# BIT_3.net
KiCad netlist of a schematic drawn in EasyEDA
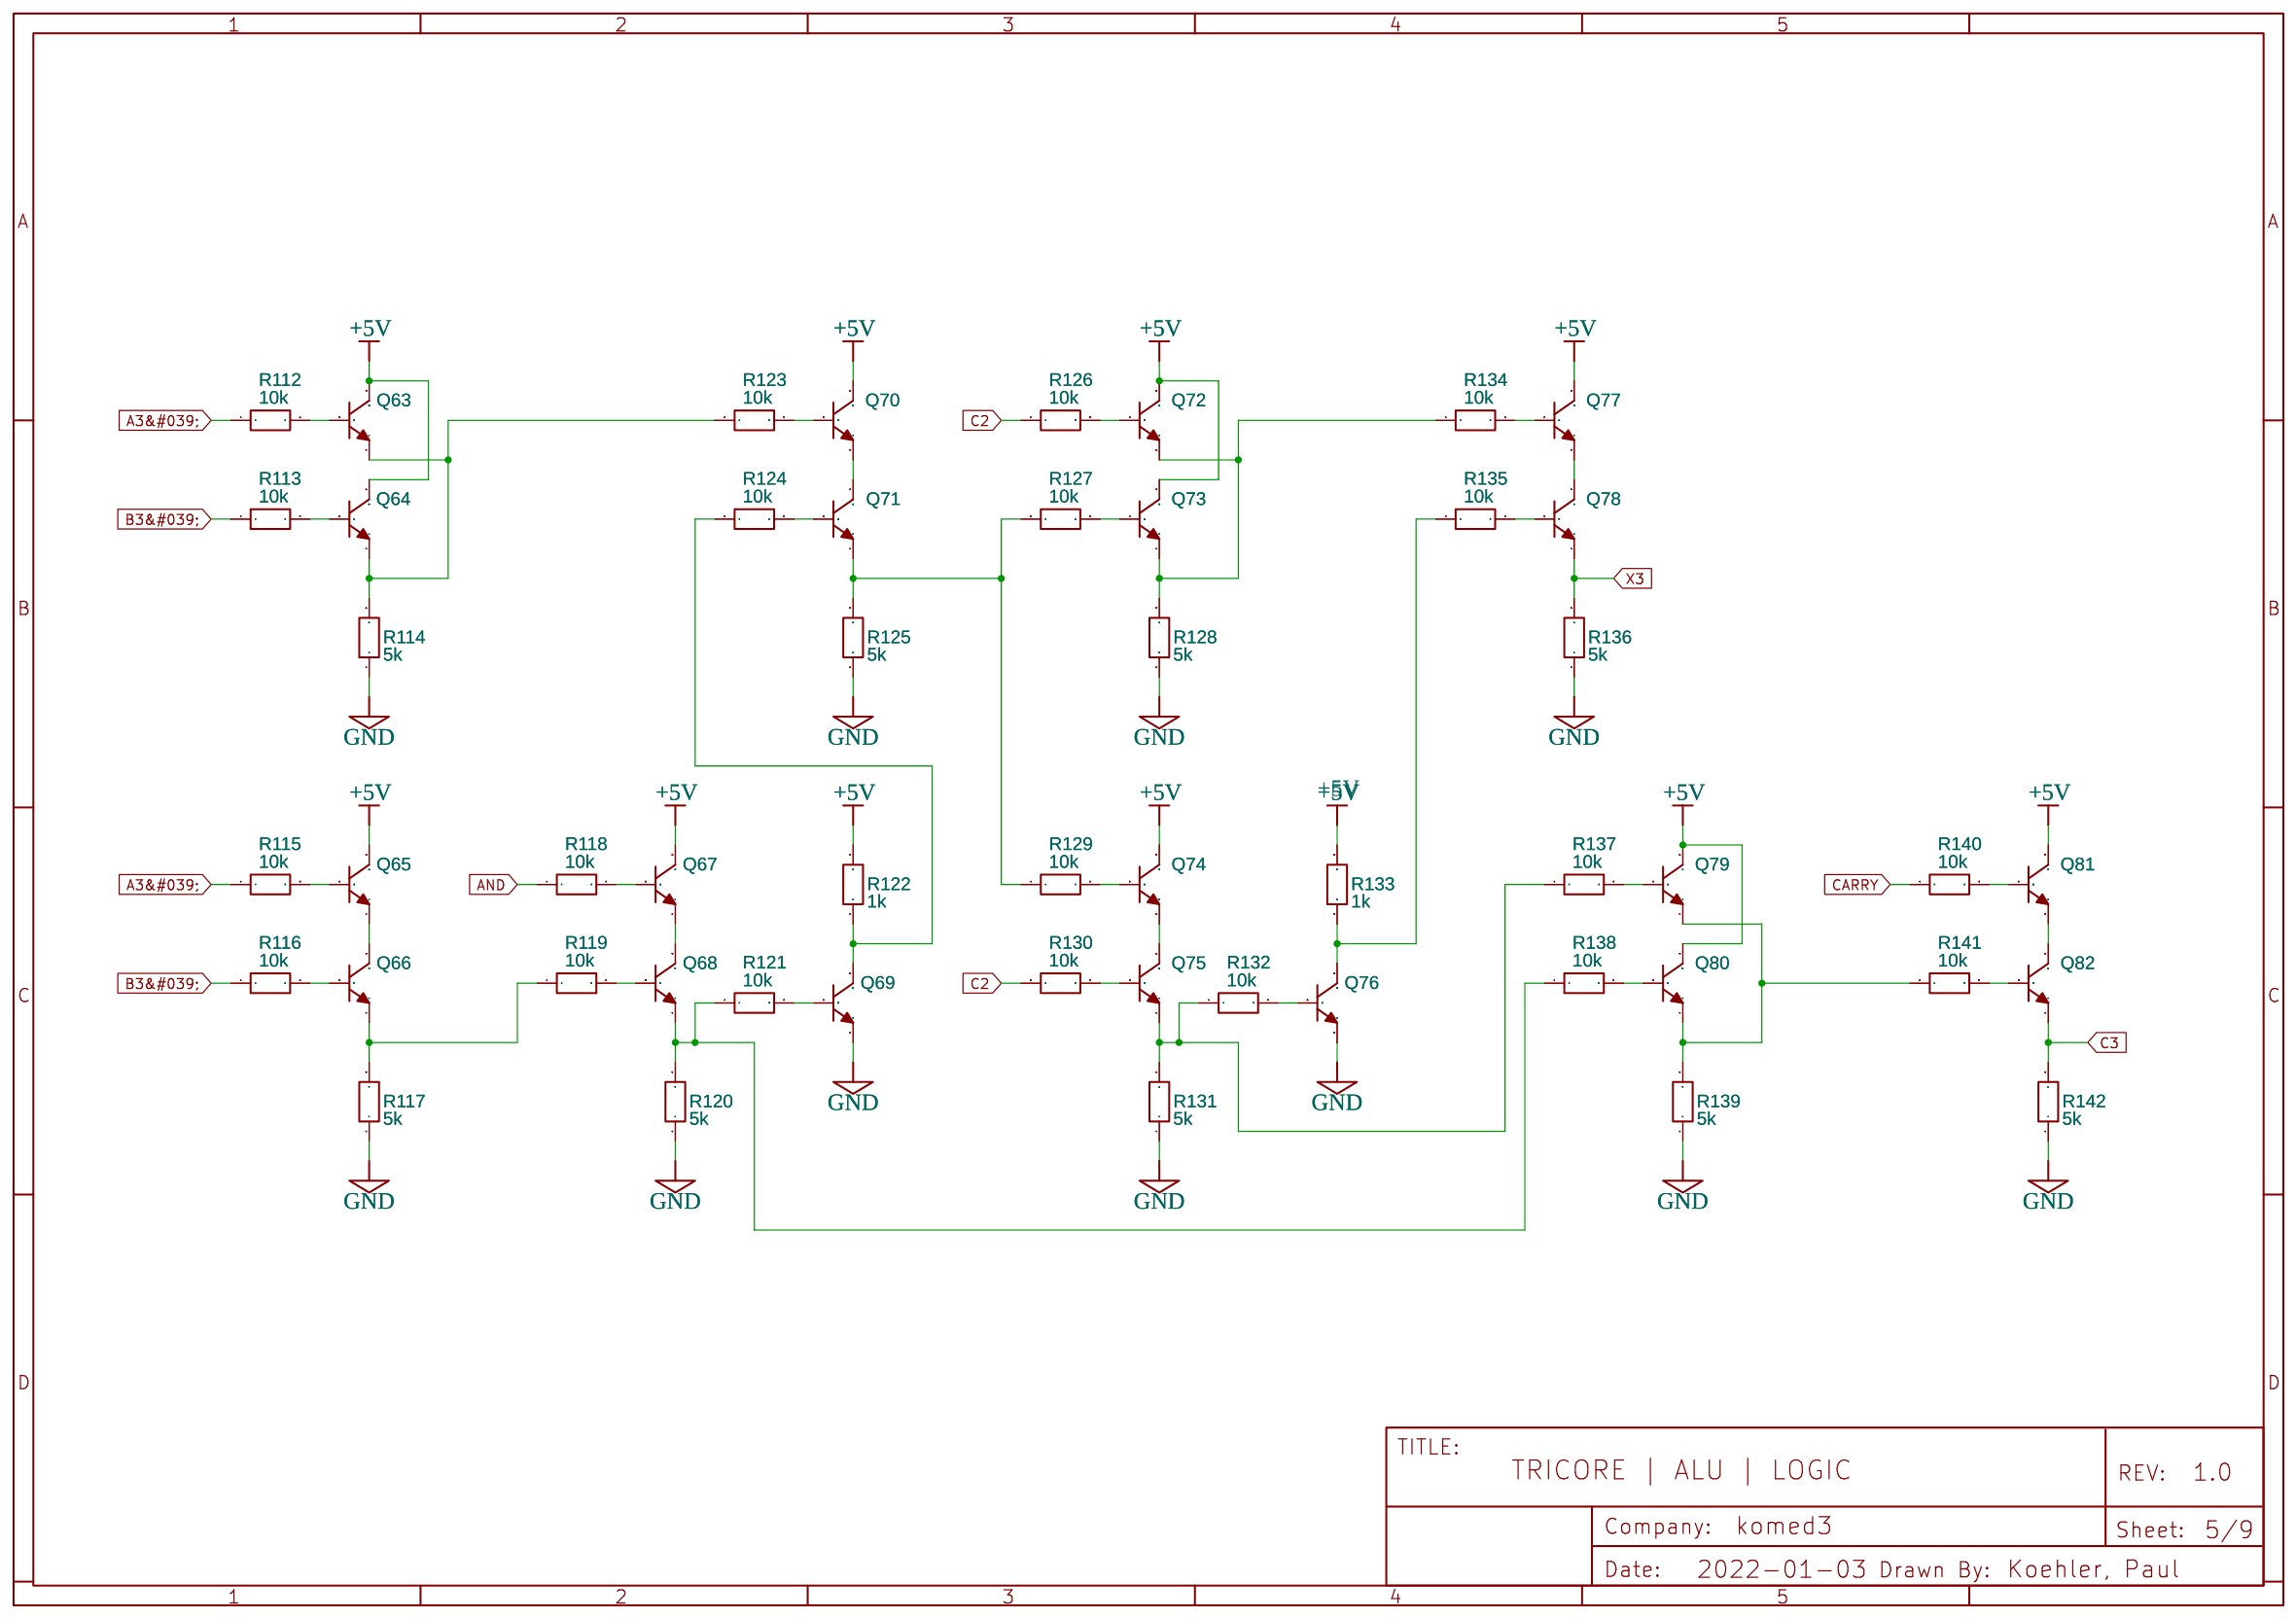
[diagram p0: schematic sheet]

(export (version "E")
  (design (tool "Eeschema 10.0.6"))
  (components
    (comp (ref "Q63")
      (value "2N3904(TO-92)")
      (fields (field (name "BOM_Manufacturer Part") "2N3904") (field (name "BOM_Supplier Part") "C118538"))
      (libsource (lib "") (part "2N3904(TO-92)"))
    )
    (comp (ref "Q64")
      (value "2N3904(TO-92)")
      (fields (field (name "BOM_Manufacturer Part") "2N3904") (field (name "BOM_Supplier Part") "C118538"))
      (libsource (lib "") (part "2N3904(TO-92)"))
    )
    (comp (ref "Q65")
      (value "2N3904(TO-92)")
      (fields (field (name "BOM_Manufacturer Part") "2N3904") (field (name "BOM_Supplier Part") "C118538"))
      (libsource (lib "") (part "2N3904(TO-92)"))
    )
    (comp (ref "Q66")
      (value "2N3904(TO-92)")
      (fields (field (name "BOM_Manufacturer Part") "2N3904") (field (name "BOM_Supplier Part") "C118538"))
      (libsource (lib "") (part "2N3904(TO-92)"))
    )
    (comp (ref "Q67")
      (value "2N3904(TO-92)")
      (fields (field (name "BOM_Manufacturer Part") "2N3904") (field (name "BOM_Supplier Part") "C118538"))
      (libsource (lib "") (part "2N3904(TO-92)"))
    )
    (comp (ref "Q68")
      (value "2N3904(TO-92)")
      (fields (field (name "BOM_Manufacturer Part") "2N3904") (field (name "BOM_Supplier Part") "C118538"))
      (libsource (lib "") (part "2N3904(TO-92)"))
    )
    (comp (ref "Q69")
      (value "2N3904(TO-92)")
      (fields (field (name "BOM_Manufacturer Part") "2N3904") (field (name "BOM_Supplier Part") "C118538"))
      (libsource (lib "") (part "2N3904(TO-92)"))
    )
    (comp (ref "Q70")
      (value "2N3904(TO-92)")
      (fields (field (name "BOM_Manufacturer Part") "2N3904") (field (name "BOM_Supplier Part") "C118538"))
      (libsource (lib "") (part "2N3904(TO-92)"))
    )
    (comp (ref "Q71")
      (value "2N3904(TO-92)")
      (fields (field (name "BOM_Manufacturer Part") "2N3904") (field (name "BOM_Supplier Part") "C118538"))
      (libsource (lib "") (part "2N3904(TO-92)"))
    )
    (comp (ref "Q72")
      (value "2N3904(TO-92)")
      (fields (field (name "BOM_Manufacturer Part") "2N3904") (field (name "BOM_Supplier Part") "C118538"))
      (libsource (lib "") (part "2N3904(TO-92)"))
    )
    (comp (ref "Q73")
      (value "2N3904(TO-92)")
      (fields (field (name "BOM_Manufacturer Part") "2N3904") (field (name "BOM_Supplier Part") "C118538"))
      (libsource (lib "") (part "2N3904(TO-92)"))
    )
    (comp (ref "Q74")
      (value "2N3904(TO-92)")
      (fields (field (name "BOM_Manufacturer Part") "2N3904") (field (name "BOM_Supplier Part") "C118538"))
      (libsource (lib "") (part "2N3904(TO-92)"))
    )
    (comp (ref "Q75")
      (value "2N3904(TO-92)")
      (fields (field (name "BOM_Manufacturer Part") "2N3904") (field (name "BOM_Supplier Part") "C118538"))
      (libsource (lib "") (part "2N3904(TO-92)"))
    )
    (comp (ref "Q76")
      (value "2N3904(TO-92)")
      (fields (field (name "BOM_Manufacturer Part") "2N3904") (field (name "BOM_Supplier Part") "C118538"))
      (libsource (lib "") (part "2N3904(TO-92)"))
    )
    (comp (ref "Q77")
      (value "2N3904(TO-92)")
      (fields (field (name "BOM_Manufacturer Part") "2N3904") (field (name "BOM_Supplier Part") "C118538"))
      (libsource (lib "") (part "2N3904(TO-92)"))
    )
    (comp (ref "Q78")
      (value "2N3904(TO-92)")
      (fields (field (name "BOM_Manufacturer Part") "2N3904") (field (name "BOM_Supplier Part") "C118538"))
      (libsource (lib "") (part "2N3904(TO-92)"))
    )
    (comp (ref "Q79")
      (value "2N3904(TO-92)")
      (fields (field (name "BOM_Manufacturer Part") "2N3904") (field (name "BOM_Supplier Part") "C118538"))
      (libsource (lib "") (part "2N3904(TO-92)"))
    )
    (comp (ref "Q80")
      (value "2N3904(TO-92)")
      (fields (field (name "BOM_Manufacturer Part") "2N3904") (field (name "BOM_Supplier Part") "C118538"))
      (libsource (lib "") (part "2N3904(TO-92)"))
    )
    (comp (ref "Q81")
      (value "2N3904(TO-92)")
      (fields (field (name "BOM_Manufacturer Part") "2N3904") (field (name "BOM_Supplier Part") "C118538"))
      (libsource (lib "") (part "2N3904(TO-92)"))
    )
    (comp (ref "Q82")
      (value "2N3904(TO-92)")
      (fields (field (name "BOM_Manufacturer Part") "2N3904") (field (name "BOM_Supplier Part") "C118538"))
      (libsource (lib "") (part "2N3904(TO-92)"))
    )
    (comp (ref "R112") (value "10k") (libsource (lib "") (part "R_AXIAL-0.3_EU")))
    (comp (ref "R113") (value "10k") (libsource (lib "") (part "R_AXIAL-0.3_EU")))
    (comp (ref "R114") (value "5k") (libsource (lib "") (part "R_AXIAL-0.3_EU_1")))
    (comp (ref "R115") (value "10k") (libsource (lib "") (part "R_AXIAL-0.3_EU")))
    (comp (ref "R116") (value "10k") (libsource (lib "") (part "R_AXIAL-0.3_EU")))
    (comp (ref "R117") (value "5k") (libsource (lib "") (part "R_AXIAL-0.3_EU_1")))
    (comp (ref "R118") (value "10k") (libsource (lib "") (part "R_AXIAL-0.3_EU")))
    (comp (ref "R119") (value "10k") (libsource (lib "") (part "R_AXIAL-0.3_EU")))
    (comp (ref "R120") (value "5k") (libsource (lib "") (part "R_AXIAL-0.3_EU_1")))
    (comp (ref "R121") (value "10k") (libsource (lib "") (part "R_AXIAL-0.3_EU")))
    (comp (ref "R122") (value "1k") (libsource (lib "") (part "R_AXIAL-0.3_EU_1")))
    (comp (ref "R123") (value "10k") (libsource (lib "") (part "R_AXIAL-0.3_EU")))
    (comp (ref "R124") (value "10k") (libsource (lib "") (part "R_AXIAL-0.3_EU")))
    (comp (ref "R125") (value "5k") (libsource (lib "") (part "R_AXIAL-0.3_EU_1")))
    (comp (ref "R126") (value "10k") (libsource (lib "") (part "R_AXIAL-0.3_EU")))
    (comp (ref "R127") (value "10k") (libsource (lib "") (part "R_AXIAL-0.3_EU")))
    (comp (ref "R128") (value "5k") (libsource (lib "") (part "R_AXIAL-0.3_EU_1")))
    (comp (ref "R129") (value "10k") (libsource (lib "") (part "R_AXIAL-0.3_EU")))
    (comp (ref "R130") (value "10k") (libsource (lib "") (part "R_AXIAL-0.3_EU")))
    (comp (ref "R131") (value "5k") (libsource (lib "") (part "R_AXIAL-0.3_EU_1")))
    (comp (ref "R132") (value "10k") (libsource (lib "") (part "R_AXIAL-0.3_EU")))
    (comp (ref "R133") (value "1k") (libsource (lib "") (part "R_AXIAL-0.3_EU_1")))
    (comp (ref "R134") (value "10k") (libsource (lib "") (part "R_AXIAL-0.3_EU")))
    (comp (ref "R135") (value "10k") (libsource (lib "") (part "R_AXIAL-0.3_EU")))
    (comp (ref "R136") (value "5k") (libsource (lib "") (part "R_AXIAL-0.3_EU_1")))
    (comp (ref "R137") (value "10k") (libsource (lib "") (part "R_AXIAL-0.3_EU")))
    (comp (ref "R138") (value "10k") (libsource (lib "") (part "R_AXIAL-0.3_EU")))
    (comp (ref "R139") (value "5k") (libsource (lib "") (part "R_AXIAL-0.3_EU_1")))
    (comp (ref "R140") (value "10k") (libsource (lib "") (part "R_AXIAL-0.3_EU")))
    (comp (ref "R141") (value "10k") (libsource (lib "") (part "R_AXIAL-0.3_EU")))
    (comp (ref "R142") (value "5k") (libsource (lib "") (part "R_AXIAL-0.3_EU_1")))
  )
  (nets
    (net (code "1") (name "+5V") (class "Default")
      (node (ref "Q63") (pin "3") (pinfunction "C_3") (pintype "unspecified"))
      (node (ref "Q64") (pin "3") (pinfunction "C_3") (pintype "unspecified"))
      (node (ref "Q65") (pin "3") (pinfunction "C_3") (pintype "unspecified"))
      (node (ref "Q67") (pin "3") (pinfunction "C_3") (pintype "unspecified"))
      (node (ref "Q70") (pin "3") (pinfunction "C_3") (pintype "unspecified"))
      (node (ref "Q72") (pin "3") (pinfunction "C_3") (pintype "unspecified"))
      (node (ref "Q73") (pin "3") (pinfunction "C_3") (pintype "unspecified"))
      (node (ref "Q74") (pin "3") (pinfunction "C_3") (pintype "unspecified"))
      (node (ref "Q77") (pin "3") (pinfunction "C_3") (pintype "unspecified"))
      (node (ref "Q79") (pin "3") (pinfunction "C_3") (pintype "unspecified"))
      (node (ref "Q80") (pin "3") (pinfunction "C_3") (pintype "unspecified"))
      (node (ref "Q81") (pin "3") (pinfunction "C_3") (pintype "unspecified"))
      (node (ref "R122") (pin "2") (pinfunction "2_2") (pintype "unspecified"))
      (node (ref "R133") (pin "2") (pinfunction "2_2") (pintype "unspecified"))
    )
    (net (code "2") (name "A3&#039;") (class "Default")
      (node (ref "R112") (pin "1") (pinfunction "1_1") (pintype "unspecified"))
      (node (ref "R115") (pin "1") (pinfunction "1_1") (pintype "unspecified"))
    )
    (net (code "3") (name "AND") (class "Default")
      (node (ref "R118") (pin "1") (pinfunction "1_1") (pintype "unspecified"))
    )
    (net (code "4") (name "B3&#039;") (class "Default")
      (node (ref "R113") (pin "1") (pinfunction "1_1") (pintype "unspecified"))
      (node (ref "R116") (pin "1") (pinfunction "1_1") (pintype "unspecified"))
    )
    (net (code "5") (name "C2") (class "Default")
      (node (ref "R126") (pin "1") (pinfunction "1_1") (pintype "unspecified"))
      (node (ref "R130") (pin "1") (pinfunction "1_1") (pintype "unspecified"))
    )
    (net (code "6") (name "C3") (class "Default")
      (node (ref "Q82") (pin "1") (pinfunction "E_1") (pintype "unspecified"))
      (node (ref "R142") (pin "2") (pinfunction "2_2") (pintype "unspecified"))
    )
    (net (code "7") (name "CARRY") (class "Default")
      (node (ref "R140") (pin "1") (pinfunction "1_1") (pintype "unspecified"))
    )
    (net (code "8") (name "GND") (class "Default")
      (node (ref "Q69") (pin "1") (pinfunction "E_1") (pintype "unspecified"))
      (node (ref "Q76") (pin "1") (pinfunction "E_1") (pintype "unspecified"))
      (node (ref "R114") (pin "1") (pinfunction "1_1") (pintype "unspecified"))
      (node (ref "R117") (pin "1") (pinfunction "1_1") (pintype "unspecified"))
      (node (ref "R120") (pin "1") (pinfunction "1_1") (pintype "unspecified"))
      (node (ref "R125") (pin "1") (pinfunction "1_1") (pintype "unspecified"))
      (node (ref "R128") (pin "1") (pinfunction "1_1") (pintype "unspecified"))
      (node (ref "R131") (pin "1") (pinfunction "1_1") (pintype "unspecified"))
      (node (ref "R136") (pin "1") (pinfunction "1_1") (pintype "unspecified"))
      (node (ref "R139") (pin "1") (pinfunction "1_1") (pintype "unspecified"))
      (node (ref "R142") (pin "1") (pinfunction "1_1") (pintype "unspecified"))
    )
    (net (code "9") (name "Net-(Q63-B)") (class "Default")
      (node (ref "Q63") (pin "2") (pinfunction "B_2") (pintype "unspecified"))
      (node (ref "R112") (pin "2") (pinfunction "2_2") (pintype "unspecified"))
    )
    (net (code "10") (name "Net-(Q63-E)") (class "Default")
      (node (ref "Q63") (pin "1") (pinfunction "E_1") (pintype "unspecified"))
      (node (ref "Q64") (pin "1") (pinfunction "E_1") (pintype "unspecified"))
      (node (ref "R114") (pin "2") (pinfunction "2_2") (pintype "unspecified"))
      (node (ref "R123") (pin "1") (pinfunction "1_1") (pintype "unspecified"))
    )
    (net (code "11") (name "Net-(Q64-B)") (class "Default")
      (node (ref "Q64") (pin "2") (pinfunction "B_2") (pintype "unspecified"))
      (node (ref "R113") (pin "2") (pinfunction "2_2") (pintype "unspecified"))
    )
    (net (code "12") (name "Net-(Q65-B)") (class "Default")
      (node (ref "Q65") (pin "2") (pinfunction "B_2") (pintype "unspecified"))
      (node (ref "R115") (pin "2") (pinfunction "2_2") (pintype "unspecified"))
    )
    (net (code "13") (name "Net-(Q65-E)") (class "Default")
      (node (ref "Q65") (pin "1") (pinfunction "E_1") (pintype "unspecified"))
      (node (ref "Q66") (pin "3") (pinfunction "C_3") (pintype "unspecified"))
    )
    (net (code "14") (name "Net-(Q66-B)") (class "Default")
      (node (ref "Q66") (pin "2") (pinfunction "B_2") (pintype "unspecified"))
      (node (ref "R116") (pin "2") (pinfunction "2_2") (pintype "unspecified"))
    )
    (net (code "15") (name "Net-(Q66-E)") (class "Default")
      (node (ref "Q66") (pin "1") (pinfunction "E_1") (pintype "unspecified"))
      (node (ref "R117") (pin "2") (pinfunction "2_2") (pintype "unspecified"))
      (node (ref "R119") (pin "1") (pinfunction "1_1") (pintype "unspecified"))
    )
    (net (code "16") (name "Net-(Q67-B)") (class "Default")
      (node (ref "Q67") (pin "2") (pinfunction "B_2") (pintype "unspecified"))
      (node (ref "R118") (pin "2") (pinfunction "2_2") (pintype "unspecified"))
    )
    (net (code "17") (name "Net-(Q67-E)") (class "Default")
      (node (ref "Q67") (pin "1") (pinfunction "E_1") (pintype "unspecified"))
      (node (ref "Q68") (pin "3") (pinfunction "C_3") (pintype "unspecified"))
    )
    (net (code "18") (name "Net-(Q68-B)") (class "Default")
      (node (ref "Q68") (pin "2") (pinfunction "B_2") (pintype "unspecified"))
      (node (ref "R119") (pin "2") (pinfunction "2_2") (pintype "unspecified"))
    )
    (net (code "19") (name "Net-(Q68-E)") (class "Default")
      (node (ref "Q68") (pin "1") (pinfunction "E_1") (pintype "unspecified"))
      (node (ref "R120") (pin "2") (pinfunction "2_2") (pintype "unspecified"))
      (node (ref "R121") (pin "1") (pinfunction "1_1") (pintype "unspecified"))
      (node (ref "R138") (pin "1") (pinfunction "1_1") (pintype "unspecified"))
    )
    (net (code "20") (name "Net-(Q69-B)") (class "Default")
      (node (ref "Q69") (pin "2") (pinfunction "B_2") (pintype "unspecified"))
      (node (ref "R121") (pin "2") (pinfunction "2_2") (pintype "unspecified"))
    )
    (net (code "21") (name "Net-(Q69-C)") (class "Default")
      (node (ref "Q69") (pin "3") (pinfunction "C_3") (pintype "unspecified"))
      (node (ref "R122") (pin "1") (pinfunction "1_1") (pintype "unspecified"))
      (node (ref "R124") (pin "1") (pinfunction "1_1") (pintype "unspecified"))
    )
    (net (code "22") (name "Net-(Q70-B)") (class "Default")
      (node (ref "Q70") (pin "2") (pinfunction "B_2") (pintype "unspecified"))
      (node (ref "R123") (pin "2") (pinfunction "2_2") (pintype "unspecified"))
    )
    (net (code "23") (name "Net-(Q70-E)") (class "Default")
      (node (ref "Q70") (pin "1") (pinfunction "E_1") (pintype "unspecified"))
      (node (ref "Q71") (pin "3") (pinfunction "C_3") (pintype "unspecified"))
    )
    (net (code "24") (name "Net-(Q71-B)") (class "Default")
      (node (ref "Q71") (pin "2") (pinfunction "B_2") (pintype "unspecified"))
      (node (ref "R124") (pin "2") (pinfunction "2_2") (pintype "unspecified"))
    )
    (net (code "25") (name "Net-(Q71-E)") (class "Default")
      (node (ref "Q71") (pin "1") (pinfunction "E_1") (pintype "unspecified"))
      (node (ref "R125") (pin "2") (pinfunction "2_2") (pintype "unspecified"))
      (node (ref "R127") (pin "1") (pinfunction "1_1") (pintype "unspecified"))
      (node (ref "R129") (pin "1") (pinfunction "1_1") (pintype "unspecified"))
    )
    (net (code "26") (name "Net-(Q72-B)") (class "Default")
      (node (ref "Q72") (pin "2") (pinfunction "B_2") (pintype "unspecified"))
      (node (ref "R126") (pin "2") (pinfunction "2_2") (pintype "unspecified"))
    )
    (net (code "27") (name "Net-(Q72-E)") (class "Default")
      (node (ref "Q72") (pin "1") (pinfunction "E_1") (pintype "unspecified"))
      (node (ref "Q73") (pin "1") (pinfunction "E_1") (pintype "unspecified"))
      (node (ref "R128") (pin "2") (pinfunction "2_2") (pintype "unspecified"))
      (node (ref "R134") (pin "1") (pinfunction "1_1") (pintype "unspecified"))
    )
    (net (code "28") (name "Net-(Q73-B)") (class "Default")
      (node (ref "Q73") (pin "2") (pinfunction "B_2") (pintype "unspecified"))
      (node (ref "R127") (pin "2") (pinfunction "2_2") (pintype "unspecified"))
    )
    (net (code "29") (name "Net-(Q74-B)") (class "Default")
      (node (ref "Q74") (pin "2") (pinfunction "B_2") (pintype "unspecified"))
      (node (ref "R129") (pin "2") (pinfunction "2_2") (pintype "unspecified"))
    )
    (net (code "30") (name "Net-(Q74-E)") (class "Default")
      (node (ref "Q74") (pin "1") (pinfunction "E_1") (pintype "unspecified"))
      (node (ref "Q75") (pin "3") (pinfunction "C_3") (pintype "unspecified"))
    )
    (net (code "31") (name "Net-(Q75-B)") (class "Default")
      (node (ref "Q75") (pin "2") (pinfunction "B_2") (pintype "unspecified"))
      (node (ref "R130") (pin "2") (pinfunction "2_2") (pintype "unspecified"))
    )
    (net (code "32") (name "Net-(Q75-E)") (class "Default")
      (node (ref "Q75") (pin "1") (pinfunction "E_1") (pintype "unspecified"))
      (node (ref "R131") (pin "2") (pinfunction "2_2") (pintype "unspecified"))
      (node (ref "R132") (pin "1") (pinfunction "1_1") (pintype "unspecified"))
      (node (ref "R137") (pin "1") (pinfunction "1_1") (pintype "unspecified"))
    )
    (net (code "33") (name "Net-(Q76-B)") (class "Default")
      (node (ref "Q76") (pin "2") (pinfunction "B_2") (pintype "unspecified"))
      (node (ref "R132") (pin "2") (pinfunction "2_2") (pintype "unspecified"))
    )
    (net (code "34") (name "Net-(Q76-C)") (class "Default")
      (node (ref "Q76") (pin "3") (pinfunction "C_3") (pintype "unspecified"))
      (node (ref "R133") (pin "1") (pinfunction "1_1") (pintype "unspecified"))
      (node (ref "R135") (pin "1") (pinfunction "1_1") (pintype "unspecified"))
    )
    (net (code "35") (name "Net-(Q77-B)") (class "Default")
      (node (ref "Q77") (pin "2") (pinfunction "B_2") (pintype "unspecified"))
      (node (ref "R134") (pin "2") (pinfunction "2_2") (pintype "unspecified"))
    )
    (net (code "36") (name "Net-(Q77-E)") (class "Default")
      (node (ref "Q77") (pin "1") (pinfunction "E_1") (pintype "unspecified"))
      (node (ref "Q78") (pin "3") (pinfunction "C_3") (pintype "unspecified"))
    )
    (net (code "37") (name "Net-(Q78-B)") (class "Default")
      (node (ref "Q78") (pin "2") (pinfunction "B_2") (pintype "unspecified"))
      (node (ref "R135") (pin "2") (pinfunction "2_2") (pintype "unspecified"))
    )
    (net (code "38") (name "Net-(Q79-B)") (class "Default")
      (node (ref "Q79") (pin "2") (pinfunction "B_2") (pintype "unspecified"))
      (node (ref "R137") (pin "2") (pinfunction "2_2") (pintype "unspecified"))
    )
    (net (code "39") (name "Net-(Q79-E)") (class "Default")
      (node (ref "Q79") (pin "1") (pinfunction "E_1") (pintype "unspecified"))
      (node (ref "Q80") (pin "1") (pinfunction "E_1") (pintype "unspecified"))
      (node (ref "R139") (pin "2") (pinfunction "2_2") (pintype "unspecified"))
      (node (ref "R141") (pin "1") (pinfunction "1_1") (pintype "unspecified"))
    )
    (net (code "40") (name "Net-(Q80-B)") (class "Default")
      (node (ref "Q80") (pin "2") (pinfunction "B_2") (pintype "unspecified"))
      (node (ref "R138") (pin "2") (pinfunction "2_2") (pintype "unspecified"))
    )
    (net (code "41") (name "Net-(Q81-B)") (class "Default")
      (node (ref "Q81") (pin "2") (pinfunction "B_2") (pintype "unspecified"))
      (node (ref "R140") (pin "2") (pinfunction "2_2") (pintype "unspecified"))
    )
    (net (code "42") (name "Net-(Q81-E)") (class "Default")
      (node (ref "Q81") (pin "1") (pinfunction "E_1") (pintype "unspecified"))
      (node (ref "Q82") (pin "3") (pinfunction "C_3") (pintype "unspecified"))
    )
    (net (code "43") (name "Net-(Q82-B)") (class "Default")
      (node (ref "Q82") (pin "2") (pinfunction "B_2") (pintype "unspecified"))
      (node (ref "R141") (pin "2") (pinfunction "2_2") (pintype "unspecified"))
    )
    (net (code "44") (name "X3") (class "Default")
      (node (ref "Q78") (pin "1") (pinfunction "E_1") (pintype "unspecified"))
      (node (ref "R136") (pin "2") (pinfunction "2_2") (pintype "unspecified"))
    )
  )
)
